# FPGA_Config.net
KiCad netlist of a schematic drawn in Altium Designer
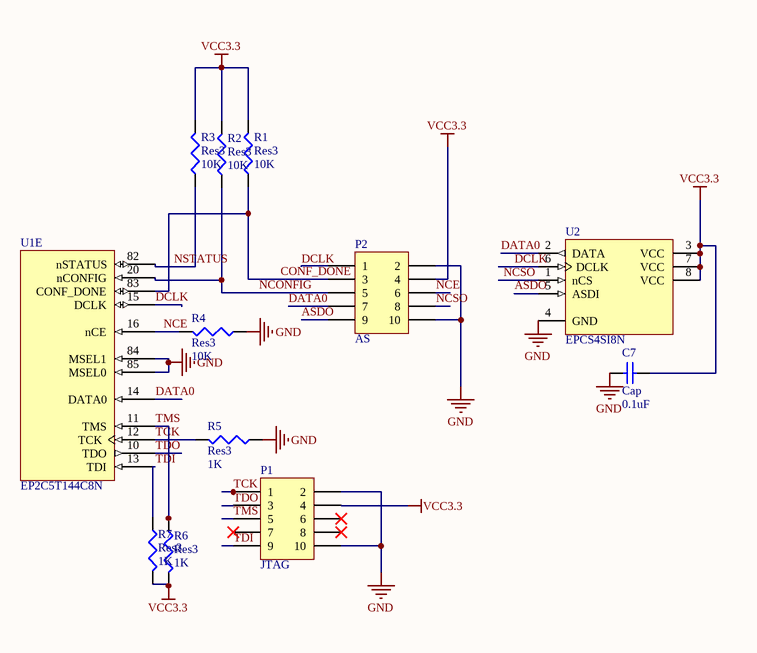
[diagram p0: FPGA Config.SchDoc]

(export (version "E")
  (design (tool "Eeschema 10.0.6"))
  (components
    (comp (ref "C7")
      (value "Cap")
      (footprint "1608[0603]")
      (description "Capacitor (Semiconductor SIM Model)")
      (fields (field (name "ALTIUM_VALUE") "0.1uF") (field (name "PUBLISHER") "Altium Limited"))
      (libsource (lib "Miscellaneous Devices") (part "Cap Semi"))
    )
    (comp (ref "P1")
      (value "JTAG")
      (footprint "HDR2X5")
      (description "Header, 5-Pin, Dual row")
      (fields (field (name "PUBLISHER") "Altium Limited"))
      (libsource (lib "Miscellaneous Connectors") (part "Header 5X2"))
    )
    (comp (ref "P2")
      (value "AS")
      (footprint "HDR2X5")
      (description "Header, 5-Pin, Dual row")
      (fields (field (name "PUBLISHER") "Altium Limited"))
      (libsource (lib "Miscellaneous Connectors") (part "Header 5X2"))
    )
    (comp (ref "R1")
      (value "Res3")
      (footprint "J1-0603")
      (description "Resistor")
      (fields (field (name "ALTIUM_VALUE") "10K") (field (name "PUBLISHER") "Altium Limited"))
      (libsource (lib "Miscellaneous Devices") (part "Res3"))
    )
    (comp (ref "R2")
      (value "Res3")
      (footprint "J1-0603")
      (description "Resistor")
      (fields (field (name "ALTIUM_VALUE") "10K") (field (name "PUBLISHER") "Altium Limited"))
      (libsource (lib "Miscellaneous Devices") (part "Res3"))
    )
    (comp (ref "R3")
      (value "Res3")
      (footprint "J1-0603")
      (description "Resistor")
      (fields (field (name "ALTIUM_VALUE") "10K") (field (name "PUBLISHER") "Altium Limited"))
      (libsource (lib "Miscellaneous Devices") (part "Res3"))
    )
    (comp (ref "R4")
      (value "Res3")
      (footprint "J1-0603")
      (description "Resistor")
      (fields (field (name "ALTIUM_VALUE") "10K") (field (name "PUBLISHER") "Altium Limited"))
      (libsource (lib "Miscellaneous Devices") (part "Res3"))
    )
    (comp (ref "R5")
      (value "Res3")
      (footprint "J1-0603")
      (description "Resistor")
      (fields (field (name "ALTIUM_VALUE") "1K") (field (name "PUBLISHER") "Altium Limited"))
      (libsource (lib "Miscellaneous Devices") (part "Res3"))
    )
    (comp (ref "R6")
      (value "Res3")
      (footprint "J1-0603")
      (description "Resistor")
      (fields (field (name "ALTIUM_VALUE") "1K") (field (name "PUBLISHER") "Altium Limited"))
      (libsource (lib "Miscellaneous Devices") (part "Res3"))
    )
    (comp (ref "R7")
      (value "Res3")
      (footprint "J1-0603")
      (description "Resistor")
      (fields (field (name "ALTIUM_VALUE") "1K") (field (name "PUBLISHER") "Altium Limited"))
      (libsource (lib "Miscellaneous Devices") (part "Res3"))
    )
    (comp (ref "U1")
      (value "EP2C5T144C8N")
      (footprint "TQFP144_N")
      (fields (field (name "PUBLISHER") "Altium Limited"))
      (libsource (lib "Altera Cyclone II") (part "EP2C5T144C8N"))
    )
    (comp (ref "U2")
      (value "EPCS4SI8N")
      (footprint "SOIC8_N")
      (fields (field (name "PUBLISHER") "Altium Limited"))
      (libsource (lib "Altera EPCS Configuration Device") (part "EPCS4SI8N"))
    )
  )
  (nets
    (net (code "1") (name "/ASDO") (class "Default")
      (node (ref "P2") (pin "9") (pinfunction "9_9") (pintype "passive"))
      (node (ref "U2") (pin "5") (pinfunction "ASDI_5") (pintype "input"))
    )
    (net (code "2") (name "/CONF_DONE") (class "Default")
      (node (ref "P2") (pin "3") (pinfunction "3_3") (pintype "passive"))
      (node (ref "R1") (pin "1") (pinfunction "1_1") (pintype "passive"))
      (node (ref "U1") (pin "83") (pinfunction "CONF_DONE_83") (pintype "bidirectional"))
    )
    (net (code "3") (name "/DATA0") (class "Default")
      (node (ref "P2") (pin "7") (pinfunction "7_7") (pintype "passive"))
      (node (ref "U1") (pin "14") (pinfunction "DATA0_14") (pintype "input"))
      (node (ref "U2") (pin "2") (pinfunction "DATA_2") (pintype "output"))
    )
    (net (code "4") (name "/DCLK") (class "Default")
      (node (ref "P2") (pin "1") (pinfunction "1_1") (pintype "passive"))
      (node (ref "U1") (pin "15") (pinfunction "DCLK_15") (pintype "bidirectional"))
      (node (ref "U2") (pin "6") (pinfunction "DCLK_6") (pintype "input"))
    )
    (net (code "5") (name "/NCE") (class "Default")
      (node (ref "P2") (pin "6") (pinfunction "6_6") (pintype "passive"))
      (node (ref "R4") (pin "2") (pinfunction "2_2") (pintype "passive"))
      (node (ref "U1") (pin "16") (pinfunction "nCE_16") (pintype "input"))
    )
    (net (code "6") (name "/NCONFIG") (class "Default")
      (node (ref "P2") (pin "5") (pinfunction "5_5") (pintype "passive"))
      (node (ref "R2") (pin "1") (pinfunction "1_1") (pintype "passive"))
      (node (ref "U1") (pin "20") (pinfunction "nCONFIG_20") (pintype "input"))
    )
    (net (code "7") (name "/NCSO") (class "Default")
      (node (ref "P2") (pin "8") (pinfunction "8_8") (pintype "passive"))
      (node (ref "U2") (pin "1") (pinfunction "nCS_1") (pintype "input"))
    )
    (net (code "8") (name "/NSTATUS") (class "Default")
      (node (ref "R3") (pin "1") (pinfunction "1_1") (pintype "passive"))
      (node (ref "U1") (pin "82") (pinfunction "nSTATUS_82") (pintype "bidirectional"))
    )
    (net (code "9") (name "/TCK") (class "Default")
      (node (ref "P1") (pin "1") (pinfunction "1_1") (pintype "passive"))
      (node (ref "R5") (pin "2") (pinfunction "2_2") (pintype "passive"))
      (node (ref "U1") (pin "12") (pinfunction "TCK_12") (pintype "input"))
    )
    (net (code "10") (name "/TDI") (class "Default")
      (node (ref "P1") (pin "9") (pinfunction "9_9") (pintype "passive"))
      (node (ref "R7") (pin "1") (pinfunction "1_1") (pintype "passive"))
      (node (ref "U1") (pin "13") (pinfunction "TDI_13") (pintype "input"))
    )
    (net (code "11") (name "/TDO") (class "Default")
      (node (ref "P1") (pin "3") (pinfunction "3_3") (pintype "passive"))
      (node (ref "U1") (pin "10") (pinfunction "TDO_10") (pintype "output"))
    )
    (net (code "12") (name "/TMS") (class "Default")
      (node (ref "P1") (pin "5") (pinfunction "5_5") (pintype "passive"))
      (node (ref "R6") (pin "1") (pinfunction "1_1") (pintype "passive"))
      (node (ref "U1") (pin "11") (pinfunction "TMS_11") (pintype "input"))
    )
    (net (code "13") (name "GND") (class "Default")
      (node (ref "C7") (pin "2") (pinfunction "2_2") (pintype "passive"))
      (node (ref "P1") (pin "10") (pinfunction "10_10") (pintype "passive"))
      (node (ref "P1") (pin "2") (pinfunction "2_2") (pintype "passive"))
      (node (ref "P2") (pin "10") (pinfunction "10_10") (pintype "passive"))
      (node (ref "P2") (pin "2") (pinfunction "2_2") (pintype "passive"))
      (node (ref "R4") (pin "1") (pinfunction "1_1") (pintype "passive"))
      (node (ref "R5") (pin "1") (pinfunction "1_1") (pintype "passive"))
      (node (ref "U1") (pin "84") (pinfunction "MSEL1_84") (pintype "input"))
      (node (ref "U1") (pin "85") (pinfunction "MSEL0_85") (pintype "input"))
      (node (ref "U2") (pin "4") (pinfunction "GND_4") (pintype "power_in"))
    )
    (net (code "14") (name "VCC3.3") (class "Default")
      (node (ref "C7") (pin "1") (pinfunction "1_1") (pintype "passive"))
      (node (ref "P1") (pin "4") (pinfunction "4_4") (pintype "passive"))
      (node (ref "P2") (pin "4") (pinfunction "4_4") (pintype "passive"))
      (node (ref "R1") (pin "2") (pinfunction "2_2") (pintype "passive"))
      (node (ref "R2") (pin "2") (pinfunction "2_2") (pintype "passive"))
      (node (ref "R3") (pin "2") (pinfunction "2_2") (pintype "passive"))
      (node (ref "R6") (pin "2") (pinfunction "2_2") (pintype "passive"))
      (node (ref "R7") (pin "2") (pinfunction "2_2") (pintype "passive"))
      (node (ref "U2") (pin "3") (pinfunction "VCC_3") (pintype "power_in"))
      (node (ref "U2") (pin "7") (pinfunction "VCC_7") (pintype "power_in"))
      (node (ref "U2") (pin "8") (pinfunction "VCC_8") (pintype "power_in"))
    )
    (net (code "15") (name "unconnected-(P1-Pad6)") (class "Default")
      (node (ref "P1") (pin "6") (pinfunction "6_6") (pintype "passive+no_connect"))
    )
    (net (code "16") (name "unconnected-(P1-Pad7)") (class "Default")
      (node (ref "P1") (pin "7") (pinfunction "7_7") (pintype "passive+no_connect"))
    )
    (net (code "17") (name "unconnected-(P1-Pad8)") (class "Default")
      (node (ref "P1") (pin "8") (pinfunction "8_8") (pintype "passive+no_connect"))
    )
  )
)
